# Relay_Board_V2.net
KiCad netlist of a schematic drawn in EAGLE
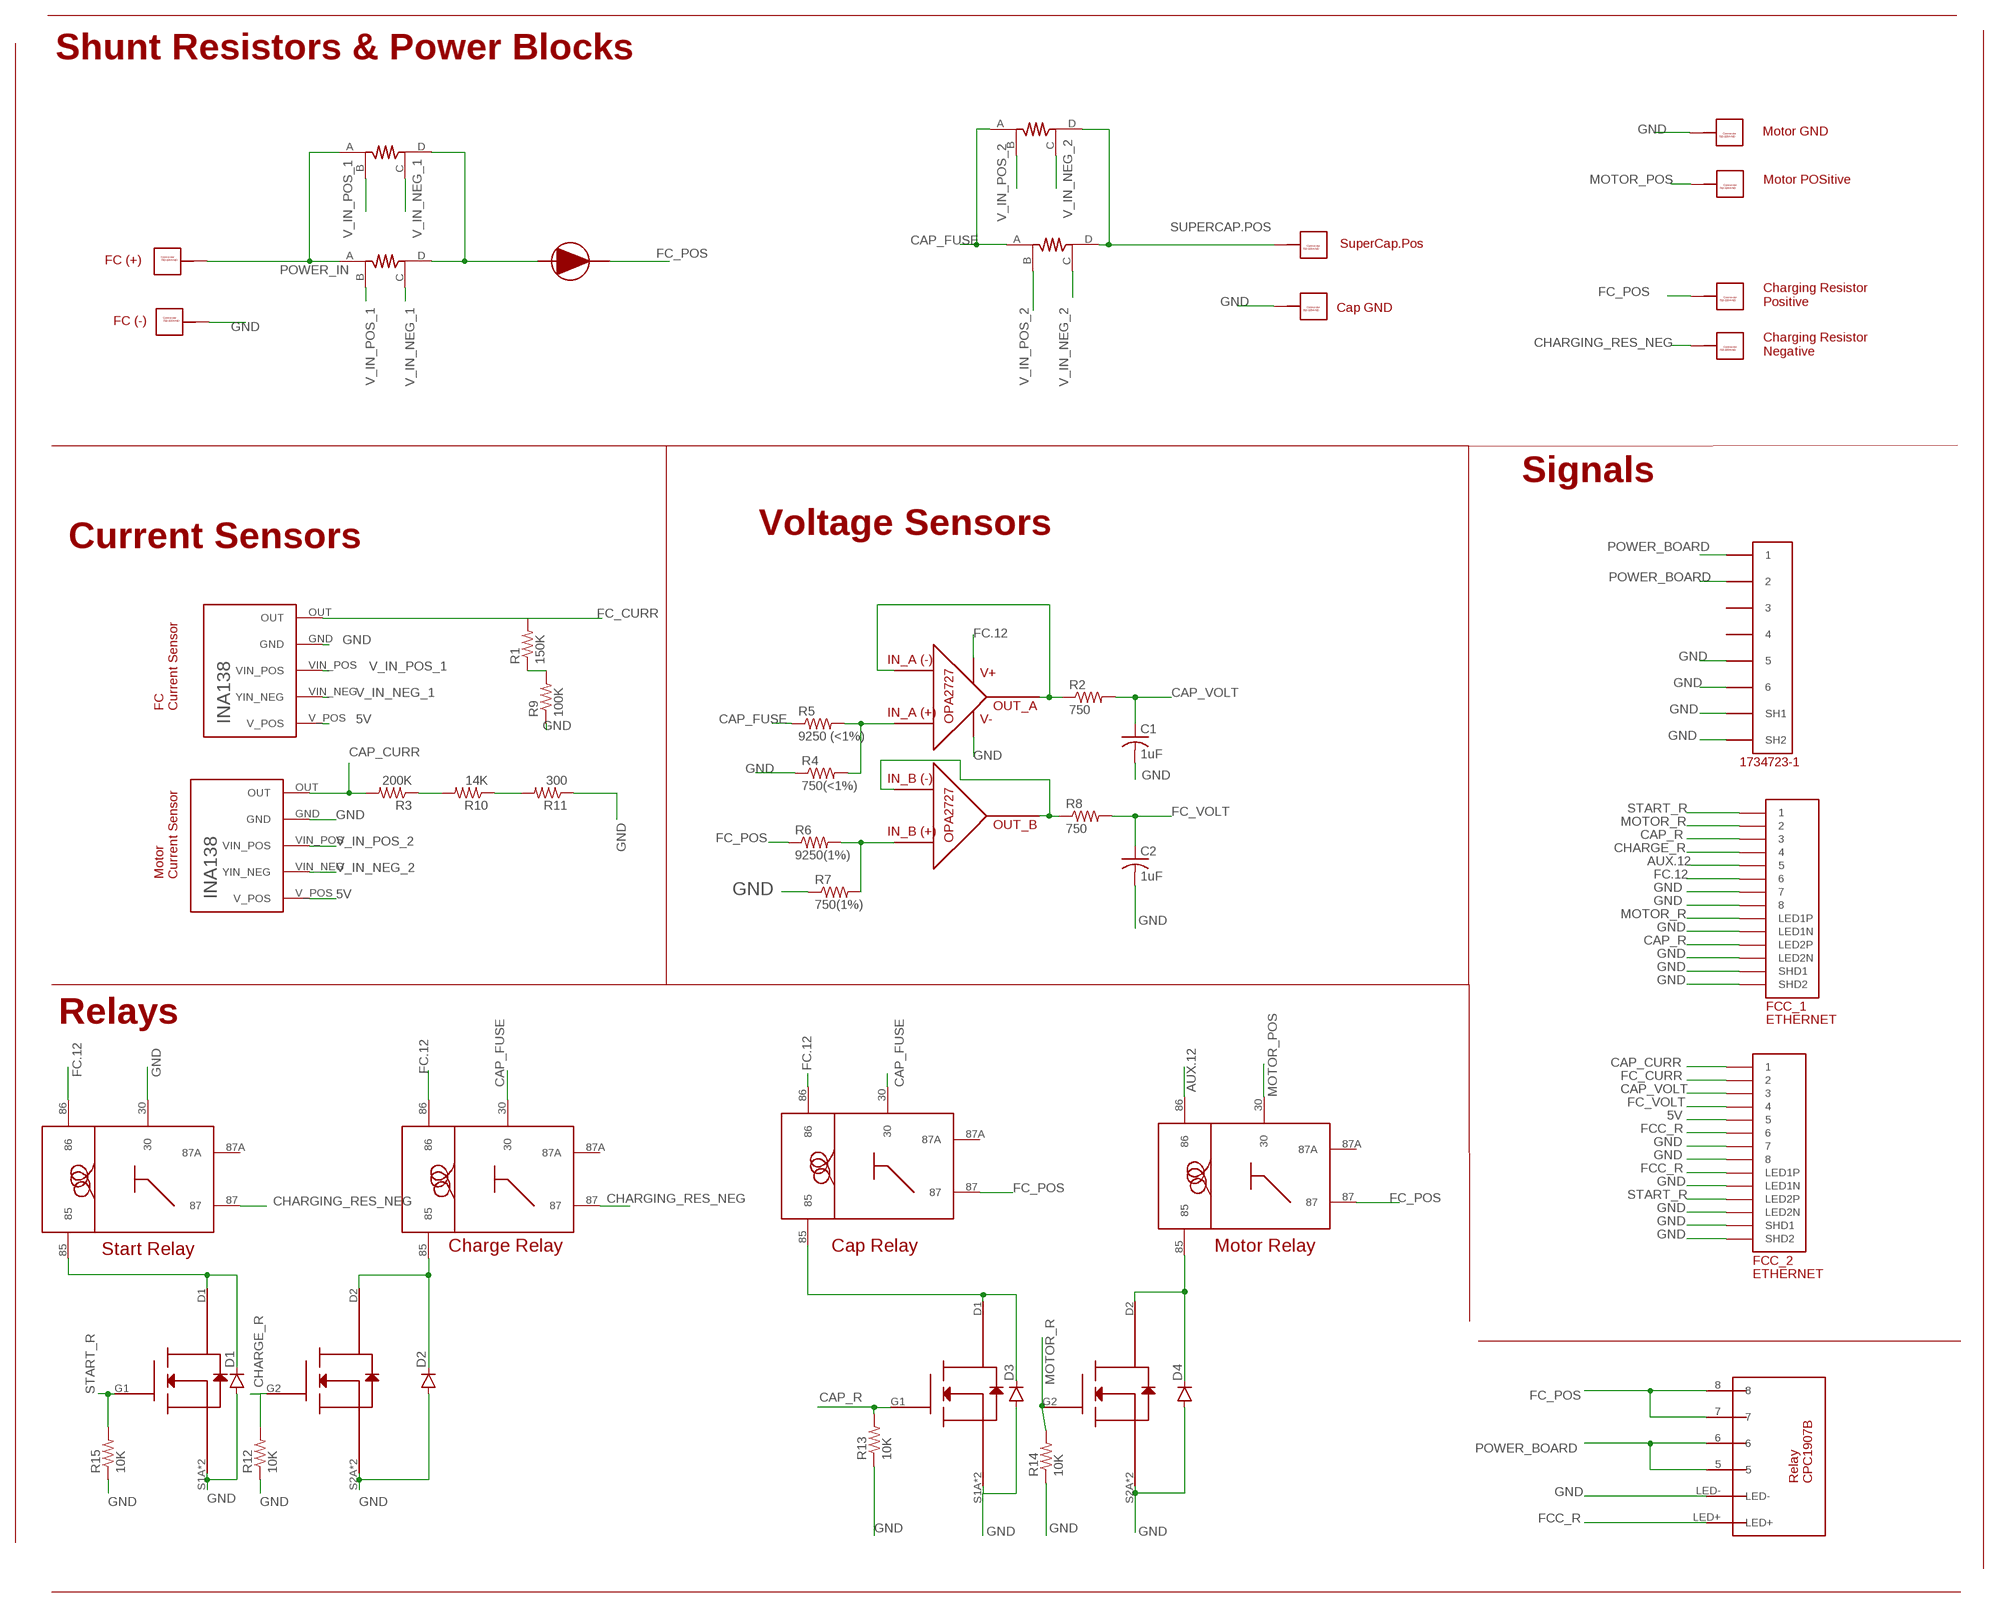
[diagram p0: schematic, sheet 1]

(export (version "E")
  (design (tool "Eeschema 10.0.6"))
  (components
    (comp (ref "C1")
      (value "1uF")
      (footprint "eagle-import:C0805")
      (libsource (lib "eagle-import") (part "C-USC0805"))
    )
    (comp (ref "C2")
      (value "1uF")
      (footprint "eagle-import:C0805")
      (libsource (lib "eagle-import") (part "C-USC0805"))
    )
    (comp (ref "CAP.GND")
      (value "732-3204-ND_CONNECTOR")
      (footprint "eagle-import:732-3204-ND")
      (libsource (lib "eagle-import") (part "732-3204-ND_CONNECTOR"))
    )
    (comp (ref "CAP.POS")
      (value "732-3204-ND_CONNECTOR")
      (footprint "eagle-import:732-3204-ND")
      (libsource (lib "eagle-import") (part "732-3204-ND_CONNECTOR"))
    )
    (comp (ref "CAP.RELAY")
      (value "VCF4-1000")
      (footprint "eagle-import:VCF4-1000")
      (libsource (lib "eagle-import") (part "VCF4-1000"))
    )
    (comp (ref "CAP.SHUNT.1")
      (value "SHUNT_RESISTOR_CSM3637")
      (footprint "eagle-import:CSM3637")
      (libsource (lib "eagle-import") (part "SHUNT_RESISTOR_CSM3637"))
    )
    (comp (ref "CAP.SHUNT.2")
      (value "SHUNT_RESISTOR_CSM3637")
      (footprint "eagle-import:CSM3637")
      (libsource (lib "eagle-import") (part "SHUNT_RESISTOR_CSM3637"))
    )
    (comp (ref "CHARGE_RELAY")
      (value "VCF4-1000")
      (footprint "eagle-import:VCF4-1000")
      (libsource (lib "eagle-import") (part "VCF4-1000"))
    )
    (comp (ref "D1")
      (value "DIODESOD123")
      (footprint "eagle-import:SOD-123")
      (libsource (lib "eagle-import") (part "DIODESOD123"))
    )
    (comp (ref "D2")
      (value "DIODESOD123")
      (footprint "eagle-import:SOD-123")
      (libsource (lib "eagle-import") (part "DIODESOD123"))
    )
    (comp (ref "D3")
      (value "DIODESOD123")
      (footprint "eagle-import:SOD-123")
      (libsource (lib "eagle-import") (part "DIODESOD123"))
    )
    (comp (ref "D4")
      (value "DIODESOD123")
      (footprint "eagle-import:SOD-123")
      (libsource (lib "eagle-import") (part "DIODESOD123"))
    )
    (comp (ref "FC.CURR.SENSOR")
      (value "TI_INA138")
      (footprint "eagle-import:TI_INA138")
      (libsource (lib "eagle-import") (part "TI_INA138"))
    )
    (comp (ref "FC.GND")
      (value "732-3204-ND_CONNECTOR")
      (footprint "eagle-import:732-3204-ND")
      (libsource (lib "eagle-import") (part "732-3204-ND_CONNECTOR"))
    )
    (comp (ref "FC.POS")
      (value "732-3204-ND_CONNECTOR")
      (footprint "eagle-import:732-3204-ND")
      (libsource (lib "eagle-import") (part "732-3204-ND_CONNECTOR"))
    )
    (comp (ref "FC.SHUNT.1")
      (value "SHUNT_RESISTOR_CSM3637")
      (footprint "eagle-import:CSM3637")
      (libsource (lib "eagle-import") (part "SHUNT_RESISTOR_CSM3637"))
    )
    (comp (ref "FC.SHUNT.2")
      (value "SHUNT_RESISTOR_CSM3637")
      (footprint "eagle-import:CSM3637")
      (libsource (lib "eagle-import") (part "SHUNT_RESISTOR_CSM3637"))
    )
    (comp (ref "FCC_1")
      (value "ETHERNET")
      (footprint "eagle-import:A122645-ND")
      (libsource (lib "eagle-import") (part "ETHERNET"))
    )
    (comp (ref "FCC_2")
      (value "ETHERNET")
      (footprint "eagle-import:A122645-ND")
      (libsource (lib "eagle-import") (part "ETHERNET"))
    )
    (comp (ref "FC_DIODE")
      (value "DIODE-APT60S20BG")
      (footprint "eagle-import:DIODE-APT60S20BG")
      (libsource (lib "eagle-import") (part "DIODE-APT60S20BG"))
    )
    (comp (ref "MOTOR.CURR.SENSOR")
      (value "TI_INA138")
      (footprint "eagle-import:TI_INA138")
      (libsource (lib "eagle-import") (part "TI_INA138"))
    )
    (comp (ref "MOTOR.GROUND")
      (value "732-3204-ND_CONNECTOR")
      (footprint "eagle-import:732-3204-ND")
      (libsource (lib "eagle-import") (part "732-3204-ND_CONNECTOR"))
    )
    (comp (ref "MOTOR.POSITIVE")
      (value "732-3204-ND_CONNECTOR")
      (footprint "eagle-import:732-3204-ND")
      (libsource (lib "eagle-import") (part "732-3204-ND_CONNECTOR"))
    )
    (comp (ref "MOTOR.RELAY")
      (value "VCF4-1000")
      (footprint "eagle-import:VCF4-1000")
      (libsource (lib "eagle-import") (part "VCF4-1000"))
    )
    (comp (ref "R1")
      (value "150K")
      (footprint "eagle-import:R0805")
      (libsource (lib "eagle-import") (part "R-US_R0805"))
    )
    (comp (ref "R2")
      (value "750")
      (footprint "eagle-import:R0805")
      (libsource (lib "eagle-import") (part "R-US_R0805"))
    )
    (comp (ref "R3")
      (value "200K")
      (footprint "eagle-import:R0805")
      (libsource (lib "eagle-import") (part "R-US_R0805"))
    )
    (comp (ref "R4")
      (value "750(<1%)")
      (footprint "eagle-import:R0805")
      (libsource (lib "eagle-import") (part "R-US_R0805"))
    )
    (comp (ref "R5")
      (value "9250 (<1%)")
      (footprint "eagle-import:R0805")
      (libsource (lib "eagle-import") (part "R-US_R0805"))
    )
    (comp (ref "R6")
      (value "9250(1%)")
      (footprint "eagle-import:R0805")
      (libsource (lib "eagle-import") (part "R-US_R0805"))
    )
    (comp (ref "R7")
      (value "750(1%)")
      (footprint "eagle-import:R0805")
      (libsource (lib "eagle-import") (part "R-US_R0805"))
    )
    (comp (ref "R8")
      (value "750")
      (footprint "eagle-import:R0805")
      (libsource (lib "eagle-import") (part "R-US_R0805"))
    )
    (comp (ref "R9")
      (value "100K")
      (footprint "eagle-import:R0805")
      (libsource (lib "eagle-import") (part "R-US_R0805"))
    )
    (comp (ref "R10")
      (value "14K")
      (footprint "eagle-import:R0805")
      (libsource (lib "eagle-import") (part "R-US_R0805"))
    )
    (comp (ref "R11")
      (value "300")
      (footprint "eagle-import:R0805")
      (libsource (lib "eagle-import") (part "R-US_R0805"))
    )
    (comp (ref "R12")
      (value "10K")
      (footprint "eagle-import:R0805")
      (libsource (lib "eagle-import") (part "R-US_R0805"))
    )
    (comp (ref "R13")
      (value "10K")
      (footprint "eagle-import:R0805")
      (libsource (lib "eagle-import") (part "R-US_R0805"))
    )
    (comp (ref "R14")
      (value "10K")
      (footprint "eagle-import:R0805")
      (libsource (lib "eagle-import") (part "R-US_R0805"))
    )
    (comp (ref "R15")
      (value "10K")
      (footprint "eagle-import:R0805")
      (libsource (lib "eagle-import") (part "R-US_R0805"))
    )
    (comp (ref "RES.NEG")
      (value "732-3204-ND_CONNECTOR")
      (footprint "eagle-import:732-3204-ND")
      (libsource (lib "eagle-import") (part "732-3204-ND_CONNECTOR"))
    )
    (comp (ref "RES.POS")
      (value "732-3204-ND_CONNECTOR")
      (footprint "eagle-import:732-3204-ND")
      (libsource (lib "eagle-import") (part "732-3204-ND_CONNECTOR"))
    )
    (comp (ref "START.RELAY")
      (value "VCF4-1000")
      (footprint "eagle-import:VCF4-1000")
      (libsource (lib "eagle-import") (part "VCF4-1000"))
    )
    (comp (ref "U$9")
      (value "SI6926ADQ-T1-E3CT-ND_MOSFET")
      (footprint "eagle-import:SI6926ADQ-T1-E3CT-ND_MOSFET")
      (libsource (lib "eagle-import") (part "SI6926ADQ-T1-E3CT-ND_MOSFET"))
    )
    (comp (ref "U$17")
      (value "OP-AMP_OPA2727AIDR")
      (footprint "eagle-import:OP-AMP_OPA2727AIDR")
      (libsource (lib "eagle-import") (part "OP-AMP_OPA2727AIDR"))
    )
    (comp (ref "U$19")
      (value "5555140-6")
      (footprint "eagle-import:1734723-1_RJ11")
      (libsource (lib "eagle-import") (part "5555140-6"))
    )
    (comp (ref "U$22")
      (value "RELAY-CPC1907B")
      (footprint "eagle-import:RELAY-CPC1907B")
      (libsource (lib "eagle-import") (part "RELAY-CPC1907B"))
    )
    (comp (ref "U$25")
      (value "SI6926ADQ-T1-E3CT-ND_MOSFET")
      (footprint "eagle-import:SI6926ADQ-T1-E3CT-ND_MOSFET")
      (libsource (lib "eagle-import") (part "SI6926ADQ-T1-E3CT-ND_MOSFET"))
    )
  )
  (nets
    (net (code "1") (name "/5V") (class "Default")
      (node (ref "FC.CURR.SENSOR") (pin "V_POS") (pinfunction "V_POS_V_POS") (pintype "bidirectional"))
      (node (ref "FCC_2") (pin "P$5") (pinfunction "5_P$5") (pintype "bidirectional"))
      (node (ref "MOTOR.CURR.SENSOR") (pin "V_POS") (pinfunction "V_POS_V_POS") (pintype "bidirectional"))
    )
    (net (code "2") (name "/AUX.12") (class "Default")
      (node (ref "FCC_1") (pin "P$5") (pinfunction "5_P$5") (pintype "bidirectional"))
      (node (ref "MOTOR.RELAY") (pin "86") (pinfunction "86_86") (pintype "bidirectional"))
    )
    (net (code "3") (name "/CAP_CURR") (class "Default")
      (node (ref "FCC_2") (pin "P$1") (pinfunction "1_P$1") (pintype "bidirectional"))
      (node (ref "MOTOR.CURR.SENSOR") (pin "OUT") (pinfunction "OUT_OUT") (pintype "bidirectional"))
      (node (ref "R3") (pin "2") (pinfunction "2_2") (pintype "passive"))
    )
    (net (code "4") (name "/CAP_FUSE") (class "Default")
      (node (ref "CAP.RELAY") (pin "30") (pinfunction "30_30") (pintype "bidirectional"))
      (node (ref "CAP.SHUNT.1") (pin "A") (pinfunction "A_A") (pintype "bidirectional"))
      (node (ref "CAP.SHUNT.2") (pin "A") (pinfunction "A_A") (pintype "bidirectional"))
      (node (ref "CHARGE_RELAY") (pin "30") (pinfunction "30_30") (pintype "bidirectional"))
      (node (ref "R5") (pin "1") (pinfunction "1_1") (pintype "passive"))
    )
    (net (code "5") (name "/CAP_R") (class "Default")
      (node (ref "FCC_1") (pin "P$12") (pinfunction "LED2P_P$12") (pintype "bidirectional"))
      (node (ref "FCC_1") (pin "P$3") (pinfunction "3_P$3") (pintype "bidirectional"))
      (node (ref "R13") (pin "2") (pinfunction "2_2") (pintype "passive"))
      (node (ref "U$9") (pin "G1") (pinfunction "G1_G1") (pintype "bidirectional"))
    )
    (net (code "6") (name "/CAP_VOLT") (class "Default")
      (node (ref "C1") (pin "1") (pinfunction "1_1") (pintype "passive"))
      (node (ref "FCC_2") (pin "P$3") (pinfunction "3_P$3") (pintype "bidirectional"))
      (node (ref "R2") (pin "2") (pinfunction "2_2") (pintype "passive"))
    )
    (net (code "7") (name "/CHARGE_R") (class "Default")
      (node (ref "FCC_1") (pin "P$4") (pinfunction "4_P$4") (pintype "bidirectional"))
      (node (ref "R12") (pin "2") (pinfunction "2_2") (pintype "passive"))
      (node (ref "U$25") (pin "G2") (pinfunction "G2_G2") (pintype "bidirectional"))
    )
    (net (code "8") (name "/CHARGING_RES_NEG") (class "Default")
      (node (ref "CHARGE_RELAY") (pin "87") (pinfunction "87_87") (pintype "bidirectional"))
      (node (ref "RES.NEG") (pin "P$1") (pinfunction "P$1_P$1") (pintype "bidirectional"))
      (node (ref "RES.NEG") (pin "P$10") (pinfunction "P$1_P$10") (pintype "bidirectional"))
      (node (ref "RES.NEG") (pin "P$2") (pinfunction "P$1_P$2") (pintype "bidirectional"))
      (node (ref "RES.NEG") (pin "P$3") (pinfunction "P$1_P$3") (pintype "bidirectional"))
      (node (ref "RES.NEG") (pin "P$4") (pinfunction "P$1_P$4") (pintype "bidirectional"))
      (node (ref "RES.NEG") (pin "P$5") (pinfunction "P$1_P$5") (pintype "bidirectional"))
      (node (ref "RES.NEG") (pin "P$6") (pinfunction "P$1_P$6") (pintype "bidirectional"))
      (node (ref "RES.NEG") (pin "P$7") (pinfunction "P$1_P$7") (pintype "bidirectional"))
      (node (ref "RES.NEG") (pin "P$8") (pinfunction "P$1_P$8") (pintype "bidirectional"))
      (node (ref "RES.NEG") (pin "P$9") (pinfunction "P$1_P$9") (pintype "bidirectional"))
      (node (ref "START.RELAY") (pin "87") (pinfunction "87_87") (pintype "bidirectional"))
    )
    (net (code "9") (name "/FC.12") (class "Default")
      (node (ref "CAP.RELAY") (pin "86") (pinfunction "86_86") (pintype "bidirectional"))
      (node (ref "CHARGE_RELAY") (pin "86") (pinfunction "86_86") (pintype "bidirectional"))
      (node (ref "FCC_1") (pin "P$6") (pinfunction "6_P$6") (pintype "bidirectional"))
      (node (ref "START.RELAY") (pin "86") (pinfunction "86_86") (pintype "bidirectional"))
      (node (ref "U$17") (pin "V+") (pinfunction "V+_V+") (pintype "bidirectional"))
    )
    (net (code "10") (name "/FCC_R") (class "Default")
      (node (ref "FCC_2") (pin "P$10") (pinfunction "LED1P_P$10") (pintype "bidirectional"))
      (node (ref "FCC_2") (pin "P$6") (pinfunction "6_P$6") (pintype "bidirectional"))
      (node (ref "U$22") (pin "LED+") (pinfunction "LED+_LED+") (pintype "bidirectional"))
    )
    (net (code "11") (name "/FC_CURR") (class "Default")
      (node (ref "FC.CURR.SENSOR") (pin "OUT") (pinfunction "OUT_OUT") (pintype "bidirectional"))
      (node (ref "FCC_2") (pin "P$2") (pinfunction "2_P$2") (pintype "bidirectional"))
      (node (ref "R1") (pin "2") (pinfunction "2_2") (pintype "passive"))
    )
    (net (code "12") (name "/FC_POS") (class "Default")
      (node (ref "CAP.RELAY") (pin "87") (pinfunction "87_87") (pintype "bidirectional"))
      (node (ref "FC_DIODE") (pin "CATHODE") (pinfunction "CATHODE_CATHODE") (pintype "output"))
      (node (ref "MOTOR.RELAY") (pin "87") (pinfunction "87_87") (pintype "bidirectional"))
      (node (ref "R6") (pin "1") (pinfunction "1_1") (pintype "passive"))
      (node (ref "RES.POS") (pin "P$1") (pinfunction "P$1_P$1") (pintype "bidirectional"))
      (node (ref "RES.POS") (pin "P$10") (pinfunction "P$1_P$10") (pintype "bidirectional"))
      (node (ref "RES.POS") (pin "P$2") (pinfunction "P$1_P$2") (pintype "bidirectional"))
      (node (ref "RES.POS") (pin "P$3") (pinfunction "P$1_P$3") (pintype "bidirectional"))
      (node (ref "RES.POS") (pin "P$4") (pinfunction "P$1_P$4") (pintype "bidirectional"))
      (node (ref "RES.POS") (pin "P$5") (pinfunction "P$1_P$5") (pintype "bidirectional"))
      (node (ref "RES.POS") (pin "P$6") (pinfunction "P$1_P$6") (pintype "bidirectional"))
      (node (ref "RES.POS") (pin "P$7") (pinfunction "P$1_P$7") (pintype "bidirectional"))
      (node (ref "RES.POS") (pin "P$8") (pinfunction "P$1_P$8") (pintype "bidirectional"))
      (node (ref "RES.POS") (pin "P$9") (pinfunction "P$1_P$9") (pintype "bidirectional"))
      (node (ref "U$22") (pin "7") (pinfunction "7_7") (pintype "bidirectional"))
      (node (ref "U$22") (pin "8") (pinfunction "8_8") (pintype "bidirectional"))
    )
    (net (code "13") (name "/FC_VOLT") (class "Default")
      (node (ref "C2") (pin "1") (pinfunction "1_1") (pintype "passive"))
      (node (ref "FCC_2") (pin "P$4") (pinfunction "4_P$4") (pintype "bidirectional"))
      (node (ref "R8") (pin "2") (pinfunction "2_2") (pintype "passive"))
    )
    (net (code "14") (name "/GND") (class "Default")
      (node (ref "C1") (pin "2") (pinfunction "2_2") (pintype "passive"))
      (node (ref "C2") (pin "2") (pinfunction "2_2") (pintype "passive"))
      (node (ref "CAP.GND") (pin "P$1") (pinfunction "P$1_P$1") (pintype "bidirectional"))
      (node (ref "CAP.GND") (pin "P$10") (pinfunction "P$1_P$10") (pintype "bidirectional"))
      (node (ref "CAP.GND") (pin "P$2") (pinfunction "P$1_P$2") (pintype "bidirectional"))
      (node (ref "CAP.GND") (pin "P$3") (pinfunction "P$1_P$3") (pintype "bidirectional"))
      (node (ref "CAP.GND") (pin "P$4") (pinfunction "P$1_P$4") (pintype "bidirectional"))
      (node (ref "CAP.GND") (pin "P$5") (pinfunction "P$1_P$5") (pintype "bidirectional"))
      (node (ref "CAP.GND") (pin "P$6") (pinfunction "P$1_P$6") (pintype "bidirectional"))
      (node (ref "CAP.GND") (pin "P$7") (pinfunction "P$1_P$7") (pintype "bidirectional"))
      (node (ref "CAP.GND") (pin "P$8") (pinfunction "P$1_P$8") (pintype "bidirectional"))
      (node (ref "CAP.GND") (pin "P$9") (pinfunction "P$1_P$9") (pintype "bidirectional"))
      (node (ref "D1") (pin "A") (pinfunction "A_A") (pintype "passive"))
      (node (ref "D2") (pin "A") (pinfunction "A_A") (pintype "passive"))
      (node (ref "D3") (pin "A") (pinfunction "A_A") (pintype "passive"))
      (node (ref "D4") (pin "A") (pinfunction "A_A") (pintype "passive"))
      (node (ref "FC.CURR.SENSOR") (pin "GND") (pinfunction "GND_GND") (pintype "bidirectional"))
      (node (ref "FC.GND") (pin "P$1") (pinfunction "P$1_P$1") (pintype "bidirectional"))
      (node (ref "FC.GND") (pin "P$10") (pinfunction "P$1_P$10") (pintype "bidirectional"))
      (node (ref "FC.GND") (pin "P$2") (pinfunction "P$1_P$2") (pintype "bidirectional"))
      (node (ref "FC.GND") (pin "P$3") (pinfunction "P$1_P$3") (pintype "bidirectional"))
      (node (ref "FC.GND") (pin "P$4") (pinfunction "P$1_P$4") (pintype "bidirectional"))
      (node (ref "FC.GND") (pin "P$5") (pinfunction "P$1_P$5") (pintype "bidirectional"))
      (node (ref "FC.GND") (pin "P$6") (pinfunction "P$1_P$6") (pintype "bidirectional"))
      (node (ref "FC.GND") (pin "P$7") (pinfunction "P$1_P$7") (pintype "bidirectional"))
      (node (ref "FC.GND") (pin "P$8") (pinfunction "P$1_P$8") (pintype "bidirectional"))
      (node (ref "FC.GND") (pin "P$9") (pinfunction "P$1_P$9") (pintype "bidirectional"))
      (node (ref "FCC_1") (pin "P$11") (pinfunction "LED2N_P$11") (pintype "bidirectional"))
      (node (ref "FCC_1") (pin "P$13") (pinfunction "SHD1_P$13") (pintype "bidirectional"))
      (node (ref "FCC_1") (pin "P$14") (pinfunction "SHD2_P$14") (pintype "bidirectional"))
      (node (ref "FCC_1") (pin "P$7") (pinfunction "7_P$7") (pintype "bidirectional"))
      (node (ref "FCC_1") (pin "P$8") (pinfunction "8_P$8") (pintype "bidirectional"))
      (node (ref "FCC_1") (pin "P$9") (pinfunction "LED1N_P$9") (pintype "bidirectional"))
      (node (ref "FCC_2") (pin "P$11") (pinfunction "LED2N_P$11") (pintype "bidirectional"))
      (node (ref "FCC_2") (pin "P$13") (pinfunction "SHD1_P$13") (pintype "bidirectional"))
      (node (ref "FCC_2") (pin "P$14") (pinfunction "SHD2_P$14") (pintype "bidirectional"))
      (node (ref "FCC_2") (pin "P$7") (pinfunction "7_P$7") (pintype "bidirectional"))
      (node (ref "FCC_2") (pin "P$8") (pinfunction "8_P$8") (pintype "bidirectional"))
      (node (ref "FCC_2") (pin "P$9") (pinfunction "LED1N_P$9") (pintype "bidirectional"))
      (node (ref "MOTOR.CURR.SENSOR") (pin "GND") (pinfunction "GND_GND") (pintype "bidirectional"))
      (node (ref "MOTOR.GROUND") (pin "P$1") (pinfunction "P$1_P$1") (pintype "bidirectional"))
      (node (ref "MOTOR.GROUND") (pin "P$10") (pinfunction "P$1_P$10") (pintype "bidirectional"))
      (node (ref "MOTOR.GROUND") (pin "P$2") (pinfunction "P$1_P$2") (pintype "bidirectional"))
      (node (ref "MOTOR.GROUND") (pin "P$3") (pinfunction "P$1_P$3") (pintype "bidirectional"))
      (node (ref "MOTOR.GROUND") (pin "P$4") (pinfunction "P$1_P$4") (pintype "bidirectional"))
      (node (ref "MOTOR.GROUND") (pin "P$5") (pinfunction "P$1_P$5") (pintype "bidirectional"))
      (node (ref "MOTOR.GROUND") (pin "P$6") (pinfunction "P$1_P$6") (pintype "bidirectional"))
      (node (ref "MOTOR.GROUND") (pin "P$7") (pinfunction "P$1_P$7") (pintype "bidirectional"))
      (node (ref "MOTOR.GROUND") (pin "P$8") (pinfunction "P$1_P$8") (pintype "bidirectional"))
      (node (ref "MOTOR.GROUND") (pin "P$9") (pinfunction "P$1_P$9") (pintype "bidirectional"))
      (node (ref "R11") (pin "1") (pinfunction "1_1") (pintype "passive"))
      (node (ref "R12") (pin "1") (pinfunction "1_1") (pintype "passive"))
      (node (ref "R13") (pin "1") (pinfunction "1_1") (pintype "passive"))
      (node (ref "R14") (pin "1") (pinfunction "1_1") (pintype "passive"))
      (node (ref "R15") (pin "1") (pinfunction "1_1") (pintype "passive"))
      (node (ref "R4") (pin "1") (pinfunction "1_1") (pintype "passive"))
      (node (ref "R7") (pin "1") (pinfunction "1_1") (pintype "passive"))
      (node (ref "R9") (pin "1") (pinfunction "1_1") (pintype "passive"))
      (node (ref "START.RELAY") (pin "30") (pinfunction "30_30") (pintype "bidirectional"))
      (node (ref "U$17") (pin "V-") (pinfunction "V-_V-") (pintype "bidirectional"))
      (node (ref "U$19") (pin "5") (pinfunction "5_5") (pintype "bidirectional"))
      (node (ref "U$19") (pin "6") (pinfunction "6_6") (pintype "bidirectional"))
      (node (ref "U$19") (pin "SH1") (pinfunction "SH1_SH1") (pintype "bidirectional"))
      (node (ref "U$19") (pin "SH2") (pinfunction "SH2_SH2") (pintype "bidirectional"))
      (node (ref "U$22") (pin "LED-") (pinfunction "LED-_LED-") (pintype "bidirectional"))
      (node (ref "U$25") (pin "S1A") (pinfunction "S1_S1A") (pintype "bidirectional"))
      (node (ref "U$25") (pin "S1B") (pinfunction "S1_S1B") (pintype "bidirectional"))
      (node (ref "U$25") (pin "S2A") (pinfunction "S2_S2A") (pintype "bidirectional"))
      (node (ref "U$25") (pin "S2B") (pinfunction "S2_S2B") (pintype "bidirectional"))
      (node (ref "U$9") (pin "S1A") (pinfunction "S1_S1A") (pintype "bidirectional"))
      (node (ref "U$9") (pin "S1B") (pinfunction "S1_S1B") (pintype "bidirectional"))
      (node (ref "U$9") (pin "S2A") (pinfunction "S2_S2A") (pintype "bidirectional"))
      (node (ref "U$9") (pin "S2B") (pinfunction "S2_S2B") (pintype "bidirectional"))
    )
    (net (code "15") (name "/MOTOR_POS") (class "Default")
      (node (ref "MOTOR.POSITIVE") (pin "P$1") (pinfunction "P$1_P$1") (pintype "bidirectional"))
      (node (ref "MOTOR.POSITIVE") (pin "P$10") (pinfunction "P$1_P$10") (pintype "bidirectional"))
      (node (ref "MOTOR.POSITIVE") (pin "P$2") (pinfunction "P$1_P$2") (pintype "bidirectional"))
      (node (ref "MOTOR.POSITIVE") (pin "P$3") (pinfunction "P$1_P$3") (pintype "bidirectional"))
      (node (ref "MOTOR.POSITIVE") (pin "P$4") (pinfunction "P$1_P$4") (pintype "bidirectional"))
      (node (ref "MOTOR.POSITIVE") (pin "P$5") (pinfunction "P$1_P$5") (pintype "bidirectional"))
      (node (ref "MOTOR.POSITIVE") (pin "P$6") (pinfunction "P$1_P$6") (pintype "bidirectional"))
      (node (ref "MOTOR.POSITIVE") (pin "P$7") (pinfunction "P$1_P$7") (pintype "bidirectional"))
      (node (ref "MOTOR.POSITIVE") (pin "P$8") (pinfunction "P$1_P$8") (pintype "bidirectional"))
      (node (ref "MOTOR.POSITIVE") (pin "P$9") (pinfunction "P$1_P$9") (pintype "bidirectional"))
      (node (ref "MOTOR.RELAY") (pin "30") (pinfunction "30_30") (pintype "bidirectional"))
    )
    (net (code "16") (name "/MOTOR_R") (class "Default")
      (node (ref "FCC_1") (pin "P$10") (pinfunction "LED1P_P$10") (pintype "bidirectional"))
      (node (ref "FCC_1") (pin "P$2") (pinfunction "2_P$2") (pintype "bidirectional"))
      (node (ref "R14") (pin "2") (pinfunction "2_2") (pintype "passive"))
      (node (ref "U$9") (pin "G2") (pinfunction "G2_G2") (pintype "bidirectional"))
    )
    (net (code "17") (name "/POWER_BOARD") (class "Default")
      (node (ref "U$19") (pin "1") (pinfunction "1_1") (pintype "bidirectional"))
      (node (ref "U$19") (pin "2") (pinfunction "2_2") (pintype "bidirectional"))
      (node (ref "U$22") (pin "5") (pinfunction "5_5") (pintype "bidirectional"))
      (node (ref "U$22") (pin "6") (pinfunction "6_6") (pintype "bidirectional"))
    )
    (net (code "18") (name "/POWER_IN") (class "Default")
      (node (ref "FC.POS") (pin "P$1") (pinfunction "P$1_P$1") (pintype "bidirectional"))
      (node (ref "FC.POS") (pin "P$10") (pinfunction "P$1_P$10") (pintype "bidirectional"))
      (node (ref "FC.POS") (pin "P$2") (pinfunction "P$1_P$2") (pintype "bidirectional"))
      (node (ref "FC.POS") (pin "P$3") (pinfunction "P$1_P$3") (pintype "bidirectional"))
      (node (ref "FC.POS") (pin "P$4") (pinfunction "P$1_P$4") (pintype "bidirectional"))
      (node (ref "FC.POS") (pin "P$5") (pinfunction "P$1_P$5") (pintype "bidirectional"))
      (node (ref "FC.POS") (pin "P$6") (pinfunction "P$1_P$6") (pintype "bidirectional"))
      (node (ref "FC.POS") (pin "P$7") (pinfunction "P$1_P$7") (pintype "bidirectional"))
      (node (ref "FC.POS") (pin "P$8") (pinfunction "P$1_P$8") (pintype "bidirectional"))
      (node (ref "FC.POS") (pin "P$9") (pinfunction "P$1_P$9") (pintype "bidirectional"))
      (node (ref "FC.SHUNT.1") (pin "A") (pinfunction "A_A") (pintype "bidirectional"))
      (node (ref "FC.SHUNT.2") (pin "A") (pinfunction "A_A") (pintype "bidirectional"))
    )
    (net (code "19") (name "/START_R") (class "Default")
      (node (ref "FCC_1") (pin "P$1") (pinfunction "1_P$1") (pintype "bidirectional"))
      (node (ref "FCC_2") (pin "P$12") (pinfunction "LED2P_P$12") (pintype "bidirectional"))
      (node (ref "R15") (pin "2") (pinfunction "2_2") (pintype "passive"))
      (node (ref "U$25") (pin "G1") (pinfunction "G1_G1") (pintype "bidirectional"))
    )
    (net (code "20") (name "/SUPERCAP.POS") (class "Default")
      (node (ref "CAP.POS") (pin "P$1") (pinfunction "P$1_P$1") (pintype "bidirectional"))
      (node (ref "CAP.POS") (pin "P$10") (pinfunction "P$1_P$10") (pintype "bidirectional"))
      (node (ref "CAP.POS") (pin "P$2") (pinfunction "P$1_P$2") (pintype "bidirectional"))
      (node (ref "CAP.POS") (pin "P$3") (pinfunction "P$1_P$3") (pintype "bidirectional"))
      (node (ref "CAP.POS") (pin "P$4") (pinfunction "P$1_P$4") (pintype "bidirectional"))
      (node (ref "CAP.POS") (pin "P$5") (pinfunction "P$1_P$5") (pintype "bidirectional"))
      (node (ref "CAP.POS") (pin "P$6") (pinfunction "P$1_P$6") (pintype "bidirectional"))
      (node (ref "CAP.POS") (pin "P$7") (pinfunction "P$1_P$7") (pintype "bidirectional"))
      (node (ref "CAP.POS") (pin "P$8") (pinfunction "P$1_P$8") (pintype "bidirectional"))
      (node (ref "CAP.POS") (pin "P$9") (pinfunction "P$1_P$9") (pintype "bidirectional"))
      (node (ref "CAP.SHUNT.1") (pin "D") (pinfunction "D_D") (pintype "bidirectional"))
      (node (ref "CAP.SHUNT.2") (pin "D") (pinfunction "D_D") (pintype "bidirectional"))
    )
    (net (code "21") (name "/V_IN_NEG_1") (class "Default")
      (node (ref "FC.CURR.SENSOR") (pin "VIN_NEG") (pinfunction "YIN_NEG_VIN_NEG") (pintype "bidirectional"))
      (node (ref "FC.SHUNT.1") (pin "C") (pinfunction "C_C") (pintype "bidirectional"))
      (node (ref "FC.SHUNT.2") (pin "C") (pinfunction "C_C") (pintype "bidirectional"))
    )
    (net (code "22") (name "/V_IN_NEG_2") (class "Default")
      (node (ref "CAP.SHUNT.1") (pin "C") (pinfunction "C_C") (pintype "bidirectional"))
      (node (ref "CAP.SHUNT.2") (pin "C") (pinfunction "C_C") (pintype "bidirectional"))
      (node (ref "MOTOR.CURR.SENSOR") (pin "VIN_NEG") (pinfunction "YIN_NEG_VIN_NEG") (pintype "bidirectional"))
    )
    (net (code "23") (name "/V_IN_POS_1") (class "Default")
      (node (ref "FC.CURR.SENSOR") (pin "VIN_POS") (pinfunction "VIN_POS_VIN_POS") (pintype "bidirectional"))
      (node (ref "FC.SHUNT.1") (pin "B") (pinfunction "B_B") (pintype "bidirectional"))
      (node (ref "FC.SHUNT.2") (pin "B") (pinfunction "B_B") (pintype "bidirectional"))
    )
    (net (code "24") (name "/V_IN_POS_2") (class "Default")
      (node (ref "CAP.SHUNT.1") (pin "B") (pinfunction "B_B") (pintype "bidirectional"))
      (node (ref "CAP.SHUNT.2") (pin "B") (pinfunction "B_B") (pintype "bidirectional"))
      (node (ref "MOTOR.CURR.SENSOR") (pin "VIN_POS") (pinfunction "VIN_POS_VIN_POS") (pintype "bidirectional"))
    )
    (net (code "25") (name "Net-(CAP.RELAY-Pad85)") (class "Default")
      (node (ref "CAP.RELAY") (pin "85") (pinfunction "85_85") (pintype "bidirectional"))
      (node (ref "D3") (pin "C") (pinfunction "C_C") (pintype "passive"))
      (node (ref "U$9") (pin "D1") (pinfunction "D1_D1") (pintype "bidirectional"))
    )
    (net (code "26") (name "Net-(CHARGE_RELAY-Pad85)") (class "Default")
      (node (ref "CHARGE_RELAY") (pin "85") (pinfunction "85_85") (pintype "bidirectional"))
      (node (ref "D2") (pin "C") (pinfunction "C_C") (pintype "passive"))
      (node (ref "U$25") (pin "D2") (pinfunction "D2_D2") (pintype "bidirectional"))
    )
    (net (code "27") (name "Net-(D1-PadC)") (class "Default")
      (node (ref "D1") (pin "C") (pinfunction "C_C") (pintype "passive"))
      (node (ref "START.RELAY") (pin "85") (pinfunction "85_85") (pintype "bidirectional"))
      (node (ref "U$25") (pin "D1") (pinfunction "D1_D1") (pintype "bidirectional"))
    )
    (net (code "28") (name "Net-(D4-PadC)") (class "Default")
      (node (ref "D4") (pin "C") (pinfunction "C_C") (pintype "passive"))
      (node (ref "MOTOR.RELAY") (pin "85") (pinfunction "85_85") (pintype "bidirectional"))
      (node (ref "U$9") (pin "D2") (pinfunction "D2_D2") (pintype "bidirectional"))
    )
    (net (code "29") (name "Net-(FC.SHUNT.1-PadD)") (class "Default")
      (node (ref "FC.SHUNT.1") (pin "D") (pinfunction "D_D") (pintype "bidirectional"))
      (node (ref "FC.SHUNT.2") (pin "D") (pinfunction "D_D") (pintype "bidirectional"))
      (node (ref "FC_DIODE") (pin "ANODE") (pinfunction "ANODE_ANODE") (pintype "input"))
    )
    (net (code "30") (name "Net-(R1-Pad1)") (class "Default")
      (node (ref "R1") (pin "1") (pinfunction "1_1") (pintype "passive"))
      (node (ref "R9") (pin "2") (pinfunction "2_2") (pintype "passive"))
    )
    (net (code "31") (name "Net-(R2-Pad1)") (class "Default")
      (node (ref "R2") (pin "1") (pinfunction "1_1") (pintype "passive"))
      (node (ref "U$17") (pin "IN_A-") (pinfunction "IN_A-_IN_A-") (pintype "bidirectional"))
      (node (ref "U$17") (pin "OUT_A") (pinfunction "OUT_A_OUT_A") (pintype "bidirectional"))
    )
    (net (code "32") (name "Net-(R4-Pad2)") (class "Default")
      (node (ref "R4") (pin "2") (pinfunction "2_2") (pintype "passive"))
      (node (ref "R5") (pin "2") (pinfunction "2_2") (pintype "passive"))
      (node (ref "U$17") (pin "IN_A+") (pinfunction "IN_A+_IN_A+") (pintype "bidirectional"))
    )
    (net (code "33") (name "Net-(R6-Pad2)") (class "Default")
      (node (ref "R6") (pin "2") (pinfunction "2_2") (pintype "passive"))
      (node (ref "R7") (pin "2") (pinfunction "2_2") (pintype "passive"))
      (node (ref "U$17") (pin "IN_B+") (pinfunction "IN_B+_IN_B+") (pintype "bidirectional"))
    )
    (net (code "34") (name "Net-(R8-Pad1)") (class "Default")
      (node (ref "R8") (pin "1") (pinfunction "1_1") (pintype "passive"))
      (node (ref "U$17") (pin "IN_B-") (pinfunction "IN_B-_IN_B-") (pintype "bidirectional"))
      (node (ref "U$17") (pin "OUT_B") (pinfunction "OUT_B_OUT_B") (pintype "bidirectional"))
    )
    (net (code "35") (name "Net-(R10-Pad1)") (class "Default")
      (node (ref "R10") (pin "1") (pinfunction "1_1") (pintype "passive"))
      (node (ref "R11") (pin "2") (pinfunction "2_2") (pintype "passive"))
    )
    (net (code "36") (name "Net-(R10-Pad2)") (class "Default")
      (node (ref "R10") (pin "2") (pinfunction "2_2") (pintype "passive"))
      (node (ref "R3") (pin "1") (pinfunction "1_1") (pintype "passive"))
    )
    (net (code "37") (name "unconnected-(CAP.RELAY-Pad87A)") (class "Default")
      (node (ref "CAP.RELAY") (pin "87A") (pinfunction "87A_87A") (pintype "bidirectional"))
    )
    (net (code "38") (name "unconnected-(CHARGE_RELAY-Pad87A)") (class "Default")
      (node (ref "CHARGE_RELAY") (pin "87A") (pinfunction "87A_87A") (pintype "bidirectional"))
    )
    (net (code "39") (name "unconnected-(MOTOR.RELAY-Pad87A)") (class "Default")
      (node (ref "MOTOR.RELAY") (pin "87A") (pinfunction "87A_87A") (pintype "bidirectional"))
    )
    (net (code "40") (name "unconnected-(START.RELAY-Pad87A)") (class "Default")
      (node (ref "START.RELAY") (pin "87A") (pinfunction "87A_87A") (pintype "bidirectional"))
    )
    (net (code "41") (name "unconnected-(U$19-Pad3)") (class "Default")
      (node (ref "U$19") (pin "3") (pinfunction "3_3") (pintype "bidirectional"))
    )
    (net (code "42") (name "unconnected-(U$19-Pad4)") (class "Default")
      (node (ref "U$19") (pin "4") (pinfunction "4_4") (pintype "bidirectional"))
    )
  )
)
